# 1_USB-TO-UART.net
KiCad netlist of a schematic drawn in Altium Designer
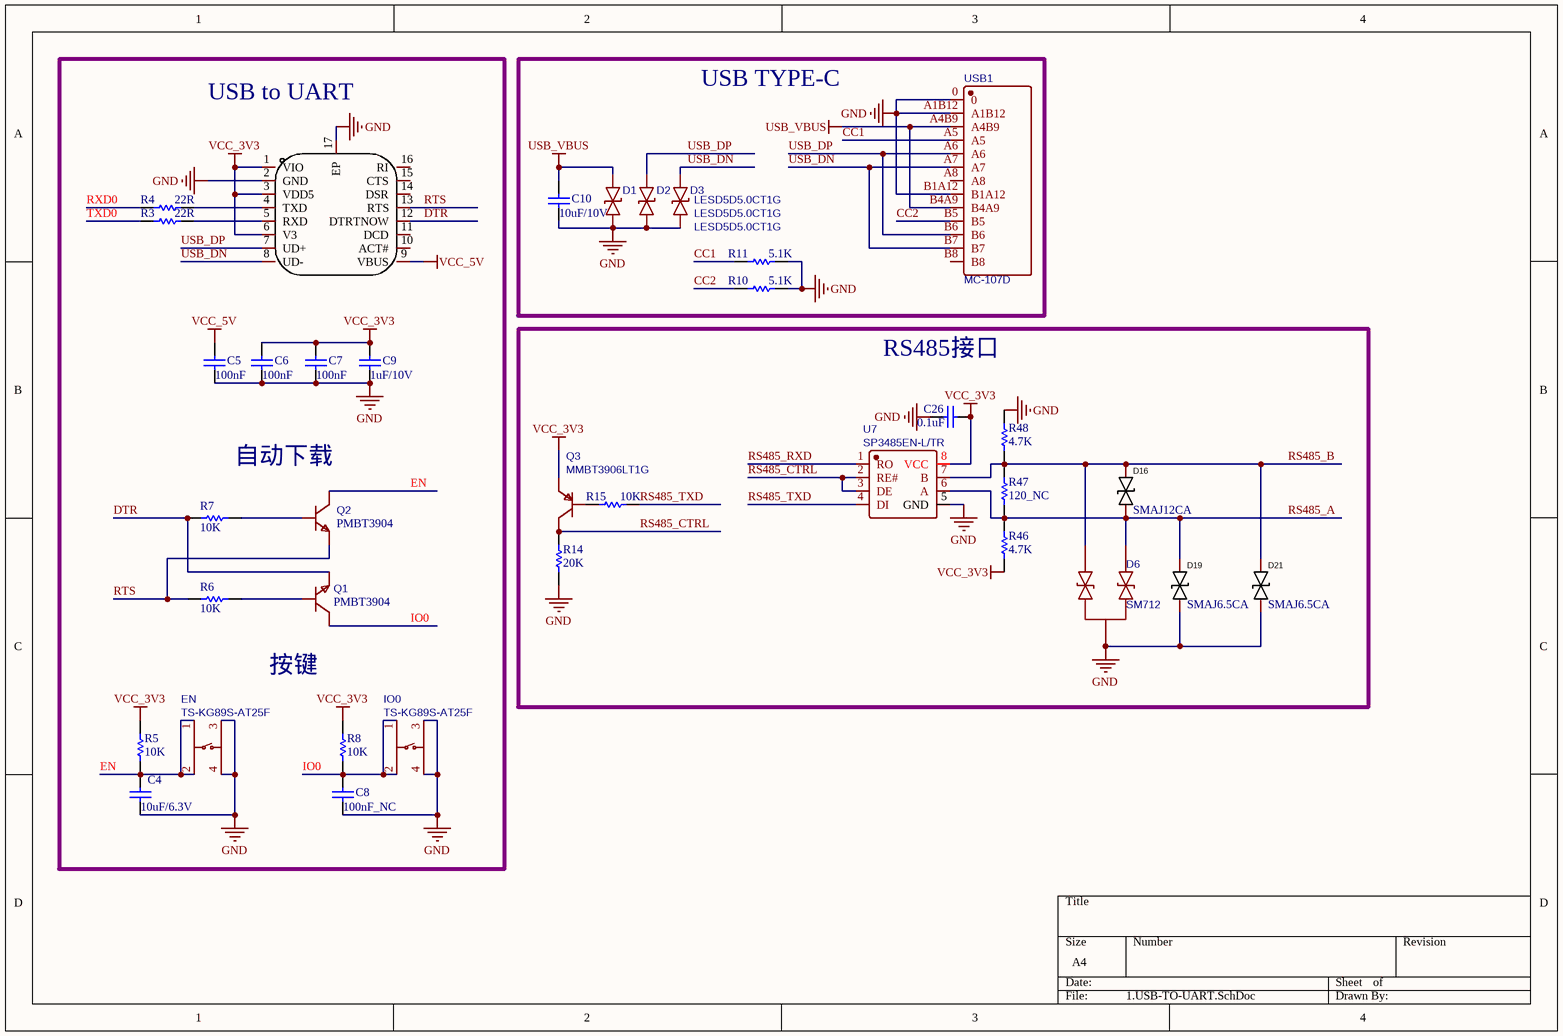
[diagram p0: 1.USB-TO-UART.SchDoc]

(export (version "E")
  (design (tool "Eeschema 10.0.6"))
  (components
    (comp (ref "C4")
      (value "10uF/6.3V")
      (footprint "0402")
      (description "Capacitor")
      (fields (field (name "PARTNUMBER") "CAP100NF") (field (name "PUBLISHER") "Altium Limited"))
      (libsource (lib "Miscellaneous Devices") (part "Cap"))
    )
    (comp (ref "C5")
      (value "100nF")
      (footprint "0402")
      (description "Capacitor")
      (fields (field (name "PARTNUMBER") "CAP100NF") (field (name "PUBLISHER") "Altium Limited"))
      (libsource (lib "Miscellaneous Devices") (part "Cap"))
    )
    (comp (ref "C6")
      (value "100nF")
      (footprint "0402")
      (description "Capacitor")
      (fields (field (name "PARTNUMBER") "CAP100NF") (field (name "PUBLISHER") "Altium Limited"))
      (libsource (lib "Miscellaneous Devices") (part "Cap"))
    )
    (comp (ref "C7")
      (value "100nF")
      (footprint "0402")
      (description "Capacitor")
      (fields (field (name "PARTNUMBER") "CAP100NF") (field (name "PUBLISHER") "Altium Limited"))
      (libsource (lib "Miscellaneous Devices") (part "Cap"))
    )
    (comp (ref "C8")
      (value "100nF_NC")
      (footprint "0402")
      (description "Capacitor")
      (fields (field (name "PARTNUMBER") "CAP100NF") (field (name "PUBLISHER") "Altium Limited"))
      (libsource (lib "Miscellaneous Devices") (part "Cap"))
    )
    (comp (ref "C9")
      (value "1uF/10V")
      (footprint "0402")
      (description "Capacitor")
      (fields (field (name "PARTNUMBER") "CAP100NF") (field (name "PUBLISHER") "Altium Limited"))
      (libsource (lib "Miscellaneous Devices") (part "Cap"))
    )
    (comp (ref "C10")
      (value "10uF/10V")
      (footprint "0402")
      (description "Capacitor")
      (fields (field (name "PARTNUMBER") "CAP100NF") (field (name "PUBLISHER") "Altium Limited"))
      (libsource (lib "Miscellaneous Devices") (part "Cap"))
    )
    (comp (ref "C26")
      (value "0.1uF")
      (footprint "0402")
      (description "Capacitor")
      (fields (field (name "PARTNUMBER") "CAP100NF") (field (name "PUBLISHER") "Altium Limited"))
      (libsource (lib "Miscellaneous Devices") (part "Cap"))
    )
    (comp (ref "D1")
      (value "LESD5D5.0CT1G")
      (footprint "SOD-523_L1.2-W0.8-LS1.6-BI")
      (fields (field (name "BOM_SUPPLIER PART") "C383211") (field (name "CONTRIBUTOR") "LCSC"))
      (libsource (lib "altium-import") (part "root_1_LESD5D5.0CT1G_"))
    )
    (comp (ref "D2")
      (value "LESD5D5.0CT1G")
      (footprint "SOD-523_L1.2-W0.8-LS1.6-BI")
      (fields (field (name "BOM_SUPPLIER PART") "C383211") (field (name "CONTRIBUTOR") "LCSC"))
      (libsource (lib "altium-import") (part "root_1_LESD5D5.0CT1G_"))
    )
    (comp (ref "D3")
      (value "LESD5D5.0CT1G")
      (footprint "SOD-523_L1.2-W0.8-LS1.6-BI")
      (fields (field (name "BOM_SUPPLIER PART") "C383211") (field (name "CONTRIBUTOR") "LCSC"))
      (libsource (lib "altium-import") (part "root_1_LESD5D5.0CT1G_"))
    )
    (comp (ref "D6")
      (value "SM712")
      (footprint "SOT-23-3_L2.9-W1.3-P1.90-LS2.4-BR")
      (fields (field (name "BOM_SUPPLIER PART") "C7420375") (field (name "CONTRIBUTOR") "LCSC"))
      (libsource (lib "HM2") (part "SM712_C521963"))
    )
    (comp (ref "D16")
      (value "SMAJ12CA")
      (footprint "SMA_L4.3-W2.6-LS5.0-BI")
      (libsource (lib "altium-import") (part "root_1_SMAJ15CA_C223985_"))
    )
    (comp (ref "D19")
      (value "SMAJ6.5CA")
      (footprint "SMA_L4.3-W2.6-LS5.0-BI")
      (libsource (lib "altium-import") (part "root_1_SMAJ15CA_C223985_"))
    )
    (comp (ref "D21")
      (value "SMAJ6.5CA")
      (footprint "SMA_L4.3-W2.6-LS5.0-BI")
      (libsource (lib "altium-import") (part "root_1_SMAJ15CA_C223985_"))
    )
    (comp (ref "EN")
      (value "TS-KG89S-AT25F")
      (footprint "SW-SMD_4P-L4.2-W3.3-P2.15-LS5.1")
      (fields (field (name "BOM_SUPPLIER PART") "C2874599") (field (name "CONTRIBUTOR") "LCSC"))
      (libsource (lib "altium-import") (part "root_3_mirrored_TS-KG89S-AT25F_"))
    )
    (comp (ref "IO0")
      (value "TS-KG89S-AT25F")
      (footprint "SW-SMD_4P-L4.2-W3.3-P2.15-LS5.1")
      (fields (field (name "BOM_SUPPLIER PART") "C2874599") (field (name "CONTRIBUTOR") "LCSC"))
      (libsource (lib "altium-import") (part "root_3_mirrored_TS-KG89S-AT25F_"))
    )
    (comp (ref "Q1")
      (value "PMBT3904")
      (footprint "SOT23")
      (libsource (lib "altium-import") (part "root_2_mirrored_BC847_C475630_"))
    )
    (comp (ref "Q2")
      (value "PMBT3904")
      (footprint "SOT23")
      (libsource (lib "altium-import") (part "root_0_BC847_C475630_"))
    )
    (comp (ref "Q3")
      (value "MMBT3906LT1G")
      (footprint "SOT-23-3_L2.9-W1.3-P1.90-LS2.4-BR")
      (fields (field (name "BOM_SUPPLIER PART") "C53444") (field (name "CONTRIBUTOR") "LCSC"))
      (libsource (lib "HM2") (part "S8550_C545533"))
    )
    (comp (ref "R3")
      (value "22R")
      (footprint "0402")
      (description "Resistor")
      (fields (field (name "PARTNUMBER") "RES22R") (field (name "PUBLISHER") "Altium Limited"))
      (libsource (lib "Miscellaneous Devices") (part "Res1"))
    )
    (comp (ref "R4")
      (value "22R")
      (footprint "0402")
      (description "Resistor")
      (fields (field (name "PARTNUMBER") "RES22R") (field (name "PUBLISHER") "Altium Limited"))
      (libsource (lib "Miscellaneous Devices") (part "Res1"))
    )
    (comp (ref "R5")
      (value "10K")
      (footprint "0402")
      (description "Resistor")
      (fields (field (name "PARTNUMBER") "RES2.2K") (field (name "PUBLISHER") "Altium Limited"))
      (libsource (lib "Miscellaneous Devices") (part "Res1"))
    )
    (comp (ref "R6")
      (value "10K")
      (footprint "0402")
      (description "Resistor")
      (fields (field (name "PARTNUMBER") "RES2.2K") (field (name "PUBLISHER") "Altium Limited"))
      (libsource (lib "Miscellaneous Devices") (part "Res1"))
    )
    (comp (ref "R7")
      (value "10K")
      (footprint "0402")
      (description "Resistor")
      (fields (field (name "PARTNUMBER") "RES2.2K") (field (name "PUBLISHER") "Altium Limited"))
      (libsource (lib "Miscellaneous Devices") (part "Res1"))
    )
    (comp (ref "R8")
      (value "10K")
      (footprint "0402")
      (description "Resistor")
      (fields (field (name "PARTNUMBER") "RES2.2K") (field (name "PUBLISHER") "Altium Limited"))
      (libsource (lib "Miscellaneous Devices") (part "Res1"))
    )
    (comp (ref "R10")
      (value "5.1K")
      (footprint "0402")
      (description "Resistor")
      (fields (field (name "PARTNUMBER") "RES2.2K") (field (name "PUBLISHER") "Altium Limited"))
      (libsource (lib "Miscellaneous Devices") (part "Res1"))
    )
    (comp (ref "R11")
      (value "5.1K")
      (footprint "0402")
      (description "Resistor")
      (fields (field (name "PARTNUMBER") "RES2.2K") (field (name "PUBLISHER") "Altium Limited"))
      (libsource (lib "Miscellaneous Devices") (part "Res1"))
    )
    (comp (ref "R14")
      (value "20K")
      (footprint "0402")
      (description "Resistor")
      (fields (field (name "PARTNUMBER") "RES2.2K") (field (name "PUBLISHER") "Altium Limited"))
      (libsource (lib "Miscellaneous Devices") (part "Res1"))
    )
    (comp (ref "R15")
      (value "10K")
      (footprint "0402")
      (description "Resistor")
      (fields (field (name "PARTNUMBER") "RES2.2K") (field (name "PUBLISHER") "Altium Limited"))
      (libsource (lib "Miscellaneous Devices") (part "Res1"))
    )
    (comp (ref "R46")
      (value "4.7K")
      (footprint "0603")
      (description "Resistor")
      (fields (field (name "PARTNUMBER") "RES22R") (field (name "PUBLISHER") "Altium Limited"))
      (libsource (lib "Miscellaneous Devices") (part "Res1"))
    )
    (comp (ref "R47")
      (value "120_NC")
      (footprint "0603")
      (description "Resistor")
      (fields (field (name "PARTNUMBER") "RES22R") (field (name "PUBLISHER") "Altium Limited"))
      (libsource (lib "Miscellaneous Devices") (part "Res1"))
    )
    (comp (ref "R48")
      (value "4.7K")
      (footprint "0603")
      (description "Resistor")
      (fields (field (name "PARTNUMBER") "RES22R") (field (name "PUBLISHER") "Altium Limited"))
      (libsource (lib "Miscellaneous Devices") (part "Res1"))
    )
    (comp (ref "U2")
      (value "CH343P")
      (footprint "TQFN-16_L3.0-W3.0-P0.50-BL-EP1.7")
      (libsource (lib "HM2") (part "CH343P"))
    )
    (comp (ref "U7")
      (value "SP3485EN-L/TR")
      (footprint "SOIC8")
      (fields (field (name "BOM_SUPPLIER PART") "C8963"))
      (libsource (lib "altium-import") (part "root_0_SP3485EN-L/TR_"))
    )
    (comp (ref "USB1")
      (value "MC-107D")
      (footprint "USB-C-SMD_MC-107D")
      (fields (field (name "BOM_SUPPLIER PART") "C2874568") (field (name "CONTRIBUTOR") "LCSC"))
      (libsource (lib "HM2") (part "MC-107D"))
    )
  )
  (nets
    (net (code "1") (name "/CC1") (class "Default")
      (node (ref "R11") (pin "2") (pinfunction "2_2") (pintype "passive"))
      (node (ref "USB1") (pin "A5") (pinfunction "A5_A5") (pintype "passive"))
    )
    (net (code "2") (name "/CC2") (class "Default")
      (node (ref "R10") (pin "2") (pinfunction "2_2") (pintype "passive"))
      (node (ref "USB1") (pin "B5") (pinfunction "B5_B5") (pintype "passive"))
    )
    (net (code "3") (name "/DTR") (class "Default")
      (node (ref "Q1") (pin "2") (pinfunction "E_2") (pintype "passive"))
      (node (ref "R7") (pin "1") (pinfunction "1_1") (pintype "passive"))
      (node (ref "U2") (pin "12") (pinfunction "DTRTNOW_12") (pintype "passive"))
    )
    (net (code "4") (name "/EN") (class "Default")
      (node (ref "C4") (pin "1") (pinfunction "1_1") (pintype "passive"))
      (node (ref "EN") (pin "1") (pinfunction "1_1") (pintype "passive"))
      (node (ref "EN") (pin "2") (pinfunction "2_2") (pintype "passive"))
      (node (ref "Q2") (pin "3") (pinfunction "C_3") (pintype "passive"))
      (node (ref "R5") (pin "1") (pinfunction "1_1") (pintype "passive"))
    )
    (net (code "5") (name "/IO0") (class "Default")
      (node (ref "C8") (pin "2") (pinfunction "2_2") (pintype "passive"))
      (node (ref "IO0") (pin "1") (pinfunction "1_1") (pintype "passive"))
      (node (ref "IO0") (pin "2") (pinfunction "2_2") (pintype "passive"))
      (node (ref "Q1") (pin "3") (pinfunction "C_3") (pintype "passive"))
      (node (ref "R8") (pin "1") (pinfunction "1_1") (pintype "passive"))
    )
    (net (code "6") (name "/RS485_A") (class "Default")
      (node (ref "D16") (pin "1") (pinfunction "1_1") (pintype "passive"))
      (node (ref "D19") (pin "2") (pinfunction "2_2") (pintype "passive"))
      (node (ref "D6") (pin "1") (pinfunction "1_1") (pintype "passive"))
      (node (ref "R46") (pin "2") (pinfunction "2_2") (pintype "passive"))
      (node (ref "R47") (pin "1") (pinfunction "1_1") (pintype "passive"))
      (node (ref "U7") (pin "6") (pinfunction "A_6") (pintype "passive"))
    )
    (net (code "7") (name "/RS485_B") (class "Default")
      (node (ref "D16") (pin "2") (pinfunction "2_2") (pintype "passive"))
      (node (ref "D21") (pin "2") (pinfunction "2_2") (pintype "passive"))
      (node (ref "D6") (pin "2") (pinfunction "2_2") (pintype "passive"))
      (node (ref "R47") (pin "2") (pinfunction "2_2") (pintype "passive"))
      (node (ref "R48") (pin "1") (pinfunction "1_1") (pintype "passive"))
      (node (ref "U7") (pin "7") (pinfunction "B_7") (pintype "passive"))
    )
    (net (code "8") (name "/RS485_CTRL") (class "Default")
      (node (ref "Q3") (pin "3") (pinfunction "C_3") (pintype "passive"))
      (node (ref "R14") (pin "1") (pinfunction "1_1") (pintype "passive"))
      (node (ref "U7") (pin "2") (pinfunction "RE#_2") (pintype "passive"))
      (node (ref "U7") (pin "3") (pinfunction "DE_3") (pintype "passive"))
    )
    (net (code "9") (name "/RS485_RXD") (class "Default")
      (node (ref "U7") (pin "1") (pinfunction "RO_1") (pintype "passive"))
    )
    (net (code "10") (name "/RS485_TXD") (class "Default")
      (node (ref "R15") (pin "1") (pinfunction "1_1") (pintype "passive"))
      (node (ref "U7") (pin "4") (pinfunction "DI_4") (pintype "passive"))
    )
    (net (code "11") (name "/RTS") (class "Default")
      (node (ref "Q2") (pin "2") (pinfunction "E_2") (pintype "passive"))
      (node (ref "R6") (pin "1") (pinfunction "1_1") (pintype "passive"))
      (node (ref "U2") (pin "13") (pinfunction "RTS_13") (pintype "passive"))
    )
    (net (code "12") (name "/RXD0") (class "Default")
      (node (ref "R4") (pin "2") (pinfunction "2_2") (pintype "passive"))
    )
    (net (code "13") (name "/TXD0") (class "Default")
      (node (ref "R3") (pin "2") (pinfunction "2_2") (pintype "passive"))
    )
    (net (code "14") (name "/USB_DN") (class "Default")
      (node (ref "D3") (pin "2") (pinfunction "2_2") (pintype "passive"))
      (node (ref "U2") (pin "8") (pinfunction "UD-_8") (pintype "passive"))
      (node (ref "USB1") (pin "A7") (pinfunction "A7_A7") (pintype "passive"))
      (node (ref "USB1") (pin "B7") (pinfunction "B7_B7") (pintype "passive"))
    )
    (net (code "15") (name "/USB_DP") (class "Default")
      (node (ref "D2") (pin "2") (pinfunction "2_2") (pintype "passive"))
      (node (ref "U2") (pin "7") (pinfunction "UD+_7") (pintype "passive"))
      (node (ref "USB1") (pin "A6") (pinfunction "A6_A6") (pintype "passive"))
      (node (ref "USB1") (pin "B6") (pinfunction "B6_B6") (pintype "passive"))
    )
    (net (code "16") (name "GND") (class "Default")
      (node (ref "C10") (pin "1") (pinfunction "1_1") (pintype "passive"))
      (node (ref "C26") (pin "1") (pinfunction "1_1") (pintype "passive"))
      (node (ref "C4") (pin "2") (pinfunction "2_2") (pintype "passive"))
      (node (ref "C5") (pin "1") (pinfunction "1_1") (pintype "passive"))
      (node (ref "C6") (pin "1") (pinfunction "1_1") (pintype "passive"))
      (node (ref "C7") (pin "1") (pinfunction "1_1") (pintype "passive"))
      (node (ref "C8") (pin "1") (pinfunction "1_1") (pintype "passive"))
      (node (ref "C9") (pin "1") (pinfunction "1_1") (pintype "passive"))
      (node (ref "D1") (pin "1") (pinfunction "1_1") (pintype "passive"))
      (node (ref "D19") (pin "1") (pinfunction "1_1") (pintype "passive"))
      (node (ref "D2") (pin "1") (pinfunction "1_1") (pintype "passive"))
      (node (ref "D21") (pin "1") (pinfunction "1_1") (pintype "passive"))
      (node (ref "D3") (pin "1") (pinfunction "1_1") (pintype "passive"))
      (node (ref "D6") (pin "3") (pinfunction "3_3") (pintype "passive"))
      (node (ref "EN") (pin "3") (pinfunction "3_3") (pintype "passive"))
      (node (ref "EN") (pin "4") (pinfunction "4_4") (pintype "passive"))
      (node (ref "IO0") (pin "3") (pinfunction "3_3") (pintype "passive"))
      (node (ref "IO0") (pin "4") (pinfunction "4_4") (pintype "passive"))
      (node (ref "R10") (pin "1") (pinfunction "1_1") (pintype "passive"))
      (node (ref "R11") (pin "1") (pinfunction "1_1") (pintype "passive"))
      (node (ref "R14") (pin "2") (pinfunction "2_2") (pintype "passive"))
      (node (ref "R48") (pin "2") (pinfunction "2_2") (pintype "passive"))
      (node (ref "U2") (pin "17") (pinfunction "EP_17") (pintype "passive"))
      (node (ref "U2") (pin "2") (pinfunction "GND_2") (pintype "passive"))
      (node (ref "U7") (pin "5") (pinfunction "GND_5") (pintype "passive"))
      (node (ref "USB1") (pin "0") (pinfunction "0_0") (pintype "passive"))
      (node (ref "USB1") (pin "A1B12") (pinfunction "A1B12_A1B12") (pintype "passive"))
      (node (ref "USB1") (pin "B1A12") (pinfunction "B1A12_B1A12") (pintype "passive"))
    )
    (net (code "17") (name "Net-(Q1-B)") (class "Default")
      (node (ref "Q1") (pin "1") (pinfunction "B_1") (pintype "passive"))
      (node (ref "R6") (pin "2") (pinfunction "2_2") (pintype "passive"))
    )
    (net (code "18") (name "Net-(Q2-B)") (class "Default")
      (node (ref "Q2") (pin "1") (pinfunction "B_1") (pintype "passive"))
      (node (ref "R7") (pin "2") (pinfunction "2_2") (pintype "passive"))
    )
    (net (code "19") (name "Net-(Q3-B)") (class "Default")
      (node (ref "Q3") (pin "1") (pinfunction "B_1") (pintype "passive"))
      (node (ref "R15") (pin "2") (pinfunction "2_2") (pintype "passive"))
    )
    (net (code "20") (name "Net-(U2-RXD)") (class "Default")
      (node (ref "R3") (pin "1") (pinfunction "1_1") (pintype "passive"))
      (node (ref "U2") (pin "5") (pinfunction "RXD_5") (pintype "passive"))
    )
    (net (code "21") (name "Net-(U2-TXD)") (class "Default")
      (node (ref "R4") (pin "1") (pinfunction "1_1") (pintype "passive"))
      (node (ref "U2") (pin "4") (pinfunction "TXD_4") (pintype "passive"))
    )
    (net (code "22") (name "USB_VBUS") (class "Default")
      (node (ref "C10") (pin "2") (pinfunction "2_2") (pintype "passive"))
      (node (ref "D1") (pin "2") (pinfunction "2_2") (pintype "passive"))
      (node (ref "USB1") (pin "A4B9") (pinfunction "A4B9_A4B9") (pintype "passive"))
      (node (ref "USB1") (pin "B4A9") (pinfunction "B4A9_B4A9") (pintype "passive"))
    )
    (net (code "23") (name "VCC_3V3") (class "Default")
      (node (ref "C26") (pin "2") (pinfunction "2_2") (pintype "passive"))
      (node (ref "C6") (pin "2") (pinfunction "2_2") (pintype "passive"))
      (node (ref "C7") (pin "2") (pinfunction "2_2") (pintype "passive"))
      (node (ref "C9") (pin "2") (pinfunction "2_2") (pintype "passive"))
      (node (ref "Q3") (pin "2") (pinfunction "E_2") (pintype "passive"))
      (node (ref "R46") (pin "1") (pinfunction "1_1") (pintype "passive"))
      (node (ref "R5") (pin "2") (pinfunction "2_2") (pintype "passive"))
      (node (ref "R8") (pin "2") (pinfunction "2_2") (pintype "passive"))
      (node (ref "U2") (pin "1") (pinfunction "VIO_1") (pintype "passive"))
      (node (ref "U2") (pin "3") (pinfunction "VDD5_3") (pintype "passive"))
      (node (ref "U2") (pin "6") (pinfunction "V3_6") (pintype "passive"))
      (node (ref "U7") (pin "8") (pinfunction "VCC_8") (pintype "passive"))
    )
    (net (code "24") (name "VCC_5V") (class "Default")
      (node (ref "C5") (pin "2") (pinfunction "2_2") (pintype "passive"))
      (node (ref "U2") (pin "9") (pinfunction "VBUS_9") (pintype "passive"))
    )
    (net (code "25") (name "unconnected-(U2-ACT#-Pad10)") (class "Default")
      (node (ref "U2") (pin "10") (pinfunction "ACT#_10") (pintype "passive"))
    )
    (net (code "26") (name "unconnected-(U2-CTS-Pad15)") (class "Default")
      (node (ref "U2") (pin "15") (pinfunction "CTS_15") (pintype "passive"))
    )
    (net (code "27") (name "unconnected-(U2-DCD-Pad11)") (class "Default")
      (node (ref "U2") (pin "11") (pinfunction "DCD_11") (pintype "passive"))
    )
    (net (code "28") (name "unconnected-(U2-DSR-Pad14)") (class "Default")
      (node (ref "U2") (pin "14") (pinfunction "DSR_14") (pintype "passive"))
    )
    (net (code "29") (name "unconnected-(U2-RI-Pad16)") (class "Default")
      (node (ref "U2") (pin "16") (pinfunction "RI_16") (pintype "passive"))
    )
    (net (code "30") (name "unconnected-(USB1-PadA8)") (class "Default")
      (node (ref "USB1") (pin "A8") (pinfunction "A8_A8") (pintype "passive"))
    )
    (net (code "31") (name "unconnected-(USB1-PadB8)") (class "Default")
      (node (ref "USB1") (pin "B8") (pinfunction "B8_B8") (pintype "passive"))
    )
  )
)
